# OttoPi02.net
KiCad netlist of a schematic drawn in EAGLE
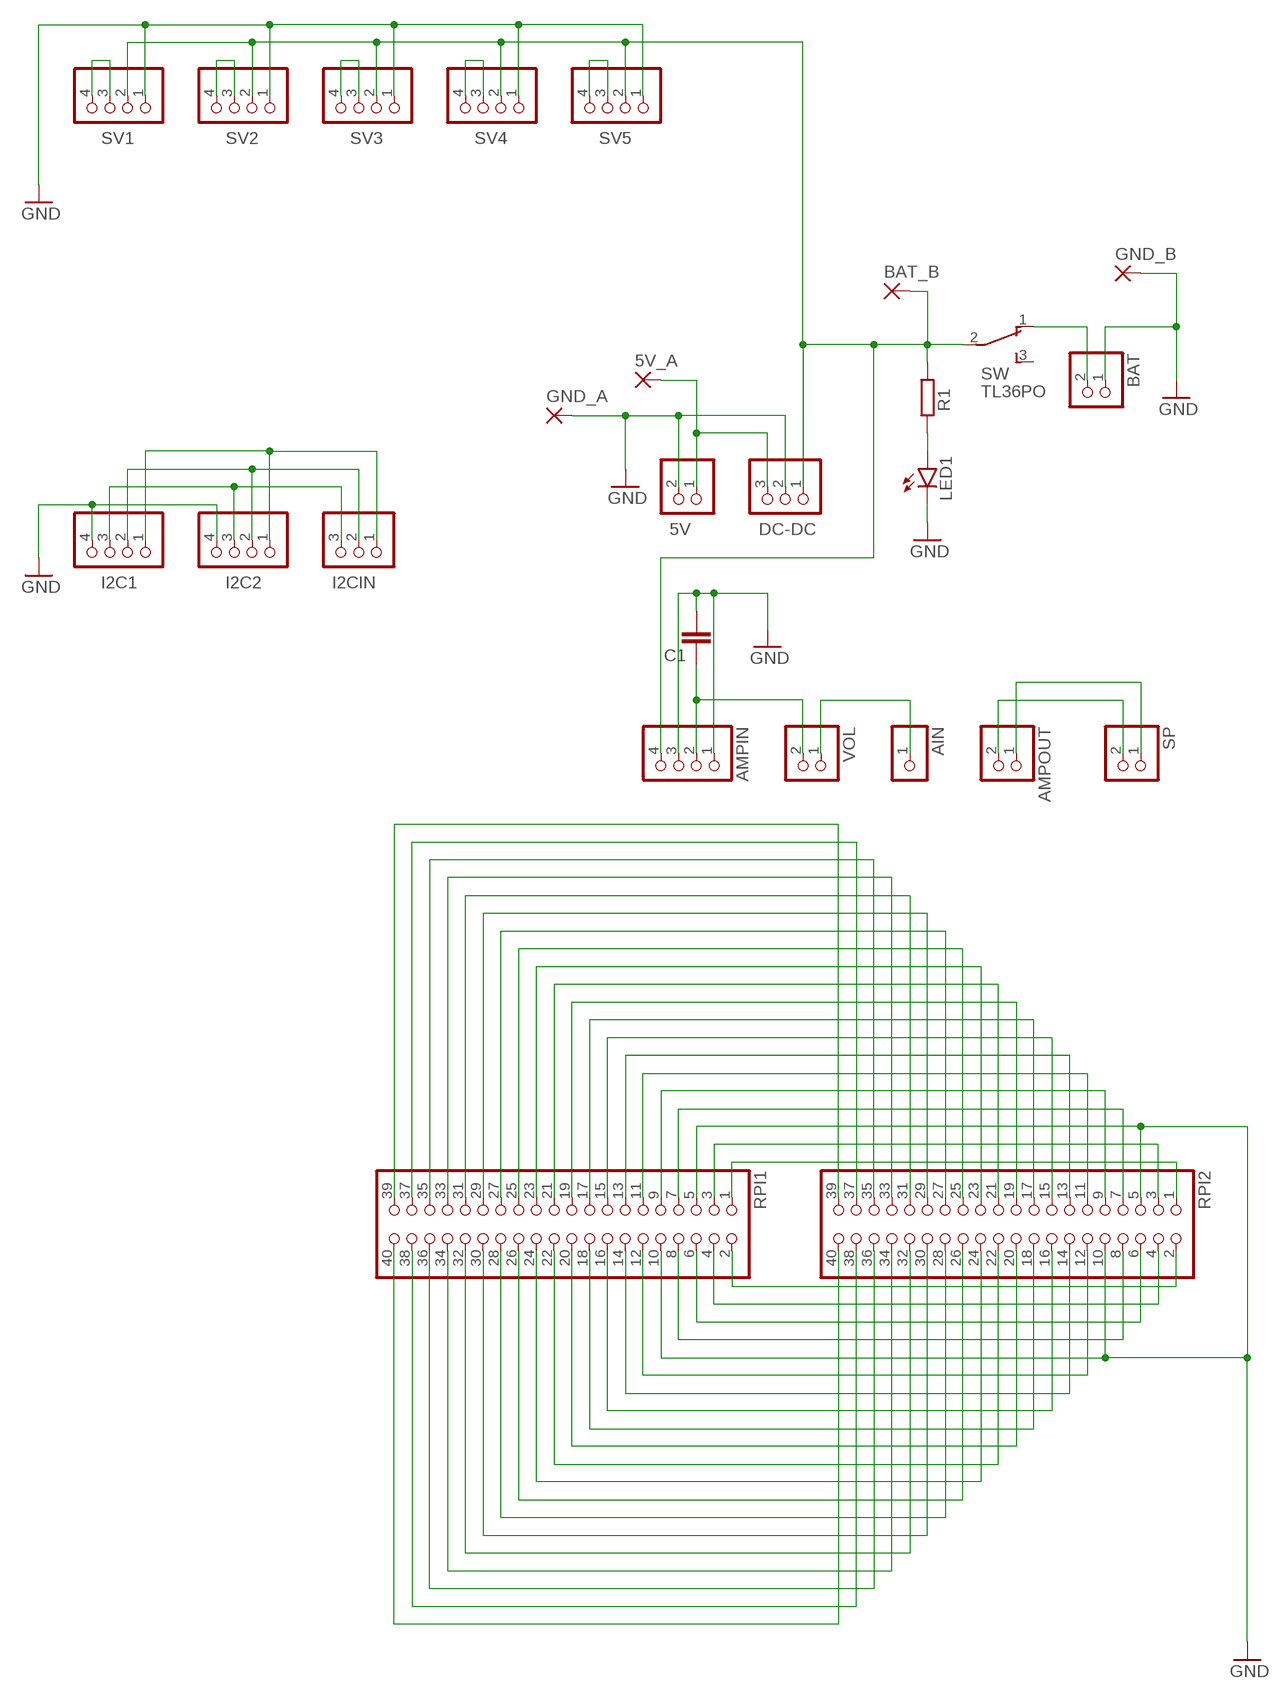
[diagram p0: schematic, sheet 1]

(export (version "E")
  (design (tool "Eeschema 10.0.6"))
  (components
    (comp (ref "5V")
      (value "PINHD-1X2")
      (footprint "eagle-import:1X02")
      (libsource (lib "eagle-import") (part "PINHD-1X2"))
    )
    (comp (ref "5V_A")
      (value "1,6/0,9")
      (footprint "eagle-import:1,6_0,9")
      (libsource (lib "eagle-import") (part "1,6/0,9"))
    )
    (comp (ref "AIN")
      (value "PINHD-1X1")
      (footprint "eagle-import:1X01")
      (libsource (lib "eagle-import") (part "PINHD-1X1"))
    )
    (comp (ref "AMPIN")
      (value "PINHD-1X4")
      (footprint "eagle-import:1X04")
      (libsource (lib "eagle-import") (part "PINHD-1X4"))
    )
    (comp (ref "AMPOUT")
      (value "PINHD-1X2")
      (footprint "eagle-import:1X02")
      (libsource (lib "eagle-import") (part "PINHD-1X2"))
    )
    (comp (ref "BAT")
      (value "PINHD-1X2")
      (footprint "eagle-import:1X02")
      (libsource (lib "eagle-import") (part "PINHD-1X2"))
    )
    (comp (ref "BAT_B")
      (value "1,6/0,9")
      (footprint "eagle-import:1,6_0,9")
      (libsource (lib "eagle-import") (part "1,6/0,9"))
    )
    (comp (ref "C1")
      (value "C-EU025-024X044")
      (footprint "eagle-import:C025-024X044")
      (libsource (lib "eagle-import") (part "C-EU025-024X044"))
    )
    (comp (ref "DC-DC")
      (value "PINHD-1X3")
      (footprint "eagle-import:1X03")
      (libsource (lib "eagle-import") (part "PINHD-1X3"))
    )
    (comp (ref "GND_A")
      (value "1,6/0,9")
      (footprint "eagle-import:1,6_0,9")
      (libsource (lib "eagle-import") (part "1,6/0,9"))
    )
    (comp (ref "GND_B")
      (value "1,6/0,9")
      (footprint "eagle-import:1,6_0,9")
      (libsource (lib "eagle-import") (part "1,6/0,9"))
    )
    (comp (ref "I2C1")
      (value "PINHD-1X4")
      (footprint "eagle-import:1X04")
      (libsource (lib "eagle-import") (part "PINHD-1X4"))
    )
    (comp (ref "I2C2")
      (value "PINHD-1X4")
      (footprint "eagle-import:1X04")
      (libsource (lib "eagle-import") (part "PINHD-1X4"))
    )
    (comp (ref "I2CIN")
      (value "PINHD-1X3")
      (footprint "eagle-import:1X03")
      (libsource (lib "eagle-import") (part "PINHD-1X3"))
    )
    (comp (ref "LED1")
      (value "LED3MM")
      (footprint "eagle-import:LED3MM")
      (libsource (lib "eagle-import") (part "LED3MM"))
    )
    (comp (ref "R1")
      (value "R-EU_0204/7")
      (footprint "eagle-import:0204_7")
      (libsource (lib "eagle-import") (part "R-EU_0204/7"))
    )
    (comp (ref "RPI1")
      (value "PINHD-2X20")
      (footprint "eagle-import:2X20")
      (libsource (lib "eagle-import") (part "PINHD-2X20"))
    )
    (comp (ref "RPI2")
      (value "PINHD-2X20")
      (footprint "eagle-import:2X20")
      (libsource (lib "eagle-import") (part "PINHD-2X20"))
    )
    (comp (ref "SP")
      (value "PINHD-1X2")
      (footprint "eagle-import:1X02")
      (libsource (lib "eagle-import") (part "PINHD-1X2"))
    )
    (comp (ref "SV1")
      (value "PINHD-1X4")
      (footprint "eagle-import:1X04")
      (libsource (lib "eagle-import") (part "PINHD-1X4"))
    )
    (comp (ref "SV2")
      (value "PINHD-1X4")
      (footprint "eagle-import:1X04")
      (libsource (lib "eagle-import") (part "PINHD-1X4"))
    )
    (comp (ref "SV3")
      (value "PINHD-1X4")
      (footprint "eagle-import:1X04")
      (libsource (lib "eagle-import") (part "PINHD-1X4"))
    )
    (comp (ref "SV4")
      (value "PINHD-1X4")
      (footprint "eagle-import:1X04")
      (libsource (lib "eagle-import") (part "PINHD-1X4"))
    )
    (comp (ref "SV5")
      (value "PINHD-1X4")
      (footprint "eagle-import:1X04")
      (libsource (lib "eagle-import") (part "PINHD-1X4"))
    )
    (comp (ref "SW")
      (value "TL36PO")
      (footprint "eagle-import:TL3XPO")
      (libsource (lib "eagle-import") (part "TL36PO"))
    )
    (comp (ref "VOL")
      (value "PINHD-1X2")
      (footprint "eagle-import:1X02")
      (libsource (lib "eagle-import") (part "PINHD-1X2"))
    )
  )
  (nets
    (net (code "1") (name "GND") (class "Default")
      (node (ref "5V") (pin "2") (pinfunction "2_2") (pintype "passive"))
      (node (ref "AMPIN") (pin "1") (pinfunction "1_1") (pintype "passive"))
      (node (ref "AMPIN") (pin "3") (pinfunction "3_3") (pintype "passive"))
      (node (ref "BAT") (pin "1") (pinfunction "1_1") (pintype "passive"))
      (node (ref "C1") (pin "2") (pinfunction "2_2") (pintype "passive"))
      (node (ref "DC-DC") (pin "2") (pinfunction "2_2") (pintype "passive"))
      (node (ref "GND_A") (pin "1") (pinfunction "P_1") (pintype "passive"))
      (node (ref "GND_B") (pin "1") (pinfunction "P_1") (pintype "passive"))
      (node (ref "I2C1") (pin "4") (pinfunction "4_4") (pintype "passive"))
      (node (ref "I2C2") (pin "4") (pinfunction "4_4") (pintype "passive"))
      (node (ref "LED1") (pin "K") (pinfunction "C_K") (pintype "passive"))
      (node (ref "RPI1") (pin "10") (pinfunction "10_10") (pintype "passive"))
      (node (ref "RPI1") (pin "5") (pinfunction "5_5") (pintype "passive"))
      (node (ref "RPI2") (pin "10") (pinfunction "10_10") (pintype "passive"))
      (node (ref "RPI2") (pin "5") (pinfunction "5_5") (pintype "passive"))
      (node (ref "SV1") (pin "1") (pinfunction "1_1") (pintype "passive"))
      (node (ref "SV2") (pin "1") (pinfunction "1_1") (pintype "passive"))
      (node (ref "SV3") (pin "1") (pinfunction "1_1") (pintype "passive"))
      (node (ref "SV4") (pin "1") (pinfunction "1_1") (pintype "passive"))
      (node (ref "SV5") (pin "1") (pinfunction "1_1") (pintype "passive"))
    )
    (net (code "2") (name "Net-(5V_A-P)") (class "Default")
      (node (ref "5V") (pin "1") (pinfunction "1_1") (pintype "passive"))
      (node (ref "5V_A") (pin "1") (pinfunction "P_1") (pintype "passive"))
      (node (ref "DC-DC") (pin "3") (pinfunction "3_3") (pintype "passive"))
    )
    (net (code "3") (name "Net-(AIN-Pad1)") (class "Default")
      (node (ref "AIN") (pin "1") (pinfunction "1_1") (pintype "passive"))
      (node (ref "VOL") (pin "1") (pinfunction "1_1") (pintype "passive"))
    )
    (net (code "4") (name "Net-(AMPIN-Pad2)") (class "Default")
      (node (ref "AMPIN") (pin "2") (pinfunction "2_2") (pintype "passive"))
      (node (ref "C1") (pin "1") (pinfunction "1_1") (pintype "passive"))
      (node (ref "VOL") (pin "2") (pinfunction "2_2") (pintype "passive"))
    )
    (net (code "5") (name "Net-(AMPOUT-Pad1)") (class "Default")
      (node (ref "AMPOUT") (pin "1") (pinfunction "1_1") (pintype "passive"))
      (node (ref "SP") (pin "1") (pinfunction "1_1") (pintype "passive"))
    )
    (net (code "6") (name "Net-(AMPOUT-Pad2)") (class "Default")
      (node (ref "AMPOUT") (pin "2") (pinfunction "2_2") (pintype "passive"))
      (node (ref "SP") (pin "2") (pinfunction "2_2") (pintype "passive"))
    )
    (net (code "7") (name "Net-(BAT_B-P)") (class "Default")
      (node (ref "AMPIN") (pin "4") (pinfunction "4_4") (pintype "passive"))
      (node (ref "BAT_B") (pin "1") (pinfunction "P_1") (pintype "passive"))
      (node (ref "DC-DC") (pin "1") (pinfunction "1_1") (pintype "passive"))
      (node (ref "R1") (pin "2") (pinfunction "2_2") (pintype "passive"))
      (node (ref "SV1") (pin "2") (pinfunction "2_2") (pintype "passive"))
      (node (ref "SV2") (pin "2") (pinfunction "2_2") (pintype "passive"))
      (node (ref "SV3") (pin "2") (pinfunction "2_2") (pintype "passive"))
      (node (ref "SV4") (pin "2") (pinfunction "2_2") (pintype "passive"))
      (node (ref "SV5") (pin "2") (pinfunction "2_2") (pintype "passive"))
      (node (ref "SW") (pin "2") (pinfunction "P_2") (pintype "passive"))
    )
    (net (code "8") (name "Net-(I2C1-Pad1)") (class "Default")
      (node (ref "I2C1") (pin "1") (pinfunction "1_1") (pintype "passive"))
      (node (ref "I2C2") (pin "1") (pinfunction "1_1") (pintype "passive"))
      (node (ref "I2CIN") (pin "1") (pinfunction "1_1") (pintype "passive"))
    )
    (net (code "9") (name "Net-(I2C1-Pad2)") (class "Default")
      (node (ref "I2C1") (pin "2") (pinfunction "2_2") (pintype "passive"))
      (node (ref "I2C2") (pin "2") (pinfunction "2_2") (pintype "passive"))
      (node (ref "I2CIN") (pin "2") (pinfunction "2_2") (pintype "passive"))
    )
    (net (code "10") (name "Net-(I2C1-Pad3)") (class "Default")
      (node (ref "I2C1") (pin "3") (pinfunction "3_3") (pintype "passive"))
      (node (ref "I2C2") (pin "3") (pinfunction "3_3") (pintype "passive"))
      (node (ref "I2CIN") (pin "3") (pinfunction "3_3") (pintype "passive"))
    )
    (net (code "11") (name "Net-(LED1-PadA)") (class "Default")
      (node (ref "LED1") (pin "A") (pinfunction "A_A") (pintype "passive"))
      (node (ref "R1") (pin "1") (pinfunction "1_1") (pintype "passive"))
    )
    (net (code "12") (name "Net-(RPI1-Pad1)") (class "Default")
      (node (ref "RPI1") (pin "1") (pinfunction "1_1") (pintype "passive"))
      (node (ref "RPI2") (pin "1") (pinfunction "1_1") (pintype "passive"))
    )
    (net (code "13") (name "Net-(RPI1-Pad2)") (class "Default")
      (node (ref "RPI1") (pin "2") (pinfunction "2_2") (pintype "passive"))
      (node (ref "RPI2") (pin "2") (pinfunction "2_2") (pintype "passive"))
    )
    (net (code "14") (name "Net-(RPI1-Pad3)") (class "Default")
      (node (ref "RPI1") (pin "3") (pinfunction "3_3") (pintype "passive"))
      (node (ref "RPI2") (pin "3") (pinfunction "3_3") (pintype "passive"))
    )
    (net (code "15") (name "Net-(RPI1-Pad4)") (class "Default")
      (node (ref "RPI1") (pin "4") (pinfunction "4_4") (pintype "passive"))
      (node (ref "RPI2") (pin "4") (pinfunction "4_4") (pintype "passive"))
    )
    (net (code "16") (name "Net-(RPI1-Pad6)") (class "Default")
      (node (ref "RPI1") (pin "6") (pinfunction "6_6") (pintype "passive"))
      (node (ref "RPI2") (pin "6") (pinfunction "6_6") (pintype "passive"))
    )
    (net (code "17") (name "Net-(RPI1-Pad7)") (class "Default")
      (node (ref "RPI1") (pin "7") (pinfunction "7_7") (pintype "passive"))
      (node (ref "RPI2") (pin "7") (pinfunction "7_7") (pintype "passive"))
    )
    (net (code "18") (name "Net-(RPI1-Pad8)") (class "Default")
      (node (ref "RPI1") (pin "8") (pinfunction "8_8") (pintype "passive"))
      (node (ref "RPI2") (pin "8") (pinfunction "8_8") (pintype "passive"))
    )
    (net (code "19") (name "Net-(RPI1-Pad9)") (class "Default")
      (node (ref "RPI1") (pin "9") (pinfunction "9_9") (pintype "passive"))
      (node (ref "RPI2") (pin "9") (pinfunction "9_9") (pintype "passive"))
    )
    (net (code "20") (name "Net-(RPI1-Pad11)") (class "Default")
      (node (ref "RPI1") (pin "11") (pinfunction "11_11") (pintype "passive"))
      (node (ref "RPI2") (pin "11") (pinfunction "11_11") (pintype "passive"))
    )
    (net (code "21") (name "Net-(RPI1-Pad12)") (class "Default")
      (node (ref "RPI1") (pin "12") (pinfunction "12_12") (pintype "passive"))
      (node (ref "RPI2") (pin "12") (pinfunction "12_12") (pintype "passive"))
    )
    (net (code "22") (name "Net-(RPI1-Pad13)") (class "Default")
      (node (ref "RPI1") (pin "13") (pinfunction "13_13") (pintype "passive"))
      (node (ref "RPI2") (pin "13") (pinfunction "13_13") (pintype "passive"))
    )
    (net (code "23") (name "Net-(RPI1-Pad14)") (class "Default")
      (node (ref "RPI1") (pin "14") (pinfunction "14_14") (pintype "passive"))
      (node (ref "RPI2") (pin "14") (pinfunction "14_14") (pintype "passive"))
    )
    (net (code "24") (name "Net-(RPI1-Pad15)") (class "Default")
      (node (ref "RPI1") (pin "15") (pinfunction "15_15") (pintype "passive"))
      (node (ref "RPI2") (pin "15") (pinfunction "15_15") (pintype "passive"))
    )
    (net (code "25") (name "Net-(RPI1-Pad16)") (class "Default")
      (node (ref "RPI1") (pin "16") (pinfunction "16_16") (pintype "passive"))
      (node (ref "RPI2") (pin "16") (pinfunction "16_16") (pintype "passive"))
    )
    (net (code "26") (name "Net-(RPI1-Pad17)") (class "Default")
      (node (ref "RPI1") (pin "17") (pinfunction "17_17") (pintype "passive"))
      (node (ref "RPI2") (pin "17") (pinfunction "17_17") (pintype "passive"))
    )
    (net (code "27") (name "Net-(RPI1-Pad18)") (class "Default")
      (node (ref "RPI1") (pin "18") (pinfunction "18_18") (pintype "passive"))
      (node (ref "RPI2") (pin "18") (pinfunction "18_18") (pintype "passive"))
    )
    (net (code "28") (name "Net-(RPI1-Pad19)") (class "Default")
      (node (ref "RPI1") (pin "19") (pinfunction "19_19") (pintype "passive"))
      (node (ref "RPI2") (pin "19") (pinfunction "19_19") (pintype "passive"))
    )
    (net (code "29") (name "Net-(RPI1-Pad20)") (class "Default")
      (node (ref "RPI1") (pin "20") (pinfunction "20_20") (pintype "passive"))
      (node (ref "RPI2") (pin "20") (pinfunction "20_20") (pintype "passive"))
    )
    (net (code "30") (name "Net-(RPI1-Pad21)") (class "Default")
      (node (ref "RPI1") (pin "21") (pinfunction "21_21") (pintype "passive"))
      (node (ref "RPI2") (pin "21") (pinfunction "21_21") (pintype "passive"))
    )
    (net (code "31") (name "Net-(RPI1-Pad22)") (class "Default")
      (node (ref "RPI1") (pin "22") (pinfunction "22_22") (pintype "passive"))
      (node (ref "RPI2") (pin "22") (pinfunction "22_22") (pintype "passive"))
    )
    (net (code "32") (name "Net-(RPI1-Pad23)") (class "Default")
      (node (ref "RPI1") (pin "23") (pinfunction "23_23") (pintype "passive"))
      (node (ref "RPI2") (pin "23") (pinfunction "23_23") (pintype "passive"))
    )
    (net (code "33") (name "Net-(RPI1-Pad24)") (class "Default")
      (node (ref "RPI1") (pin "24") (pinfunction "24_24") (pintype "passive"))
      (node (ref "RPI2") (pin "24") (pinfunction "24_24") (pintype "passive"))
    )
    (net (code "34") (name "Net-(RPI1-Pad25)") (class "Default")
      (node (ref "RPI1") (pin "25") (pinfunction "25_25") (pintype "passive"))
      (node (ref "RPI2") (pin "25") (pinfunction "25_25") (pintype "passive"))
    )
    (net (code "35") (name "Net-(RPI1-Pad26)") (class "Default")
      (node (ref "RPI1") (pin "26") (pinfunction "26_26") (pintype "passive"))
      (node (ref "RPI2") (pin "26") (pinfunction "26_26") (pintype "passive"))
    )
    (net (code "36") (name "Net-(RPI1-Pad27)") (class "Default")
      (node (ref "RPI1") (pin "27") (pinfunction "27_27") (pintype "passive"))
      (node (ref "RPI2") (pin "27") (pinfunction "27_27") (pintype "passive"))
    )
    (net (code "37") (name "Net-(RPI1-Pad28)") (class "Default")
      (node (ref "RPI1") (pin "28") (pinfunction "28_28") (pintype "passive"))
      (node (ref "RPI2") (pin "28") (pinfunction "28_28") (pintype "passive"))
    )
    (net (code "38") (name "Net-(RPI1-Pad29)") (class "Default")
      (node (ref "RPI1") (pin "29") (pinfunction "29_29") (pintype "passive"))
      (node (ref "RPI2") (pin "29") (pinfunction "29_29") (pintype "passive"))
    )
    (net (code "39") (name "Net-(RPI1-Pad30)") (class "Default")
      (node (ref "RPI1") (pin "30") (pinfunction "30_30") (pintype "passive"))
      (node (ref "RPI2") (pin "30") (pinfunction "30_30") (pintype "passive"))
    )
    (net (code "40") (name "Net-(RPI1-Pad31)") (class "Default")
      (node (ref "RPI1") (pin "31") (pinfunction "31_31") (pintype "passive"))
      (node (ref "RPI2") (pin "31") (pinfunction "31_31") (pintype "passive"))
    )
    (net (code "41") (name "Net-(RPI1-Pad32)") (class "Default")
      (node (ref "RPI1") (pin "32") (pinfunction "32_32") (pintype "passive"))
      (node (ref "RPI2") (pin "32") (pinfunction "32_32") (pintype "passive"))
    )
    (net (code "42") (name "Net-(RPI1-Pad33)") (class "Default")
      (node (ref "RPI1") (pin "33") (pinfunction "33_33") (pintype "passive"))
      (node (ref "RPI2") (pin "33") (pinfunction "33_33") (pintype "passive"))
    )
    (net (code "43") (name "Net-(RPI1-Pad34)") (class "Default")
      (node (ref "RPI1") (pin "34") (pinfunction "34_34") (pintype "passive"))
      (node (ref "RPI2") (pin "34") (pinfunction "34_34") (pintype "passive"))
    )
    (net (code "44") (name "Net-(RPI1-Pad35)") (class "Default")
      (node (ref "RPI1") (pin "35") (pinfunction "35_35") (pintype "passive"))
      (node (ref "RPI2") (pin "35") (pinfunction "35_35") (pintype "passive"))
    )
    (net (code "45") (name "Net-(RPI1-Pad36)") (class "Default")
      (node (ref "RPI1") (pin "36") (pinfunction "36_36") (pintype "passive"))
      (node (ref "RPI2") (pin "36") (pinfunction "36_36") (pintype "passive"))
    )
    (net (code "46") (name "Net-(RPI1-Pad37)") (class "Default")
      (node (ref "RPI1") (pin "37") (pinfunction "37_37") (pintype "passive"))
      (node (ref "RPI2") (pin "37") (pinfunction "37_37") (pintype "passive"))
    )
    (net (code "47") (name "Net-(RPI1-Pad38)") (class "Default")
      (node (ref "RPI1") (pin "38") (pinfunction "38_38") (pintype "passive"))
      (node (ref "RPI2") (pin "38") (pinfunction "38_38") (pintype "passive"))
    )
    (net (code "48") (name "Net-(RPI1-Pad39)") (class "Default")
      (node (ref "RPI1") (pin "39") (pinfunction "39_39") (pintype "passive"))
      (node (ref "RPI2") (pin "39") (pinfunction "39_39") (pintype "passive"))
    )
    (net (code "49") (name "Net-(RPI1-Pad40)") (class "Default")
      (node (ref "RPI1") (pin "40") (pinfunction "40_40") (pintype "passive"))
      (node (ref "RPI2") (pin "40") (pinfunction "40_40") (pintype "passive"))
    )
    (net (code "50") (name "Net-(SV1-Pad3)") (class "Default")
      (node (ref "SV1") (pin "3") (pinfunction "3_3") (pintype "passive"))
      (node (ref "SV1") (pin "4") (pinfunction "4_4") (pintype "passive"))
    )
    (net (code "51") (name "Net-(SV2-Pad3)") (class "Default")
      (node (ref "SV2") (pin "3") (pinfunction "3_3") (pintype "passive"))
      (node (ref "SV2") (pin "4") (pinfunction "4_4") (pintype "passive"))
    )
    (net (code "52") (name "Net-(SV3-Pad3)") (class "Default")
      (node (ref "SV3") (pin "3") (pinfunction "3_3") (pintype "passive"))
      (node (ref "SV3") (pin "4") (pinfunction "4_4") (pintype "passive"))
    )
    (net (code "53") (name "Net-(SV4-Pad3)") (class "Default")
      (node (ref "SV4") (pin "3") (pinfunction "3_3") (pintype "passive"))
      (node (ref "SV4") (pin "4") (pinfunction "4_4") (pintype "passive"))
    )
    (net (code "54") (name "Net-(SV5-Pad3)") (class "Default")
      (node (ref "SV5") (pin "3") (pinfunction "3_3") (pintype "passive"))
      (node (ref "SV5") (pin "4") (pinfunction "4_4") (pintype "passive"))
    )
    (net (code "55") (name "Net-(SW-O)") (class "Default")
      (node (ref "BAT") (pin "2") (pinfunction "2_2") (pintype "passive"))
      (node (ref "SW") (pin "1") (pinfunction "O_1") (pintype "passive"))
    )
    (net (code "56") (name "unconnected-(SW-S-Pad3)") (class "Default")
      (node (ref "SW") (pin "3") (pinfunction "S_3") (pintype "passive"))
    )
  )
)
